# DefaultProject.net
KiCad netlist of a schematic drawn in Altium Designer
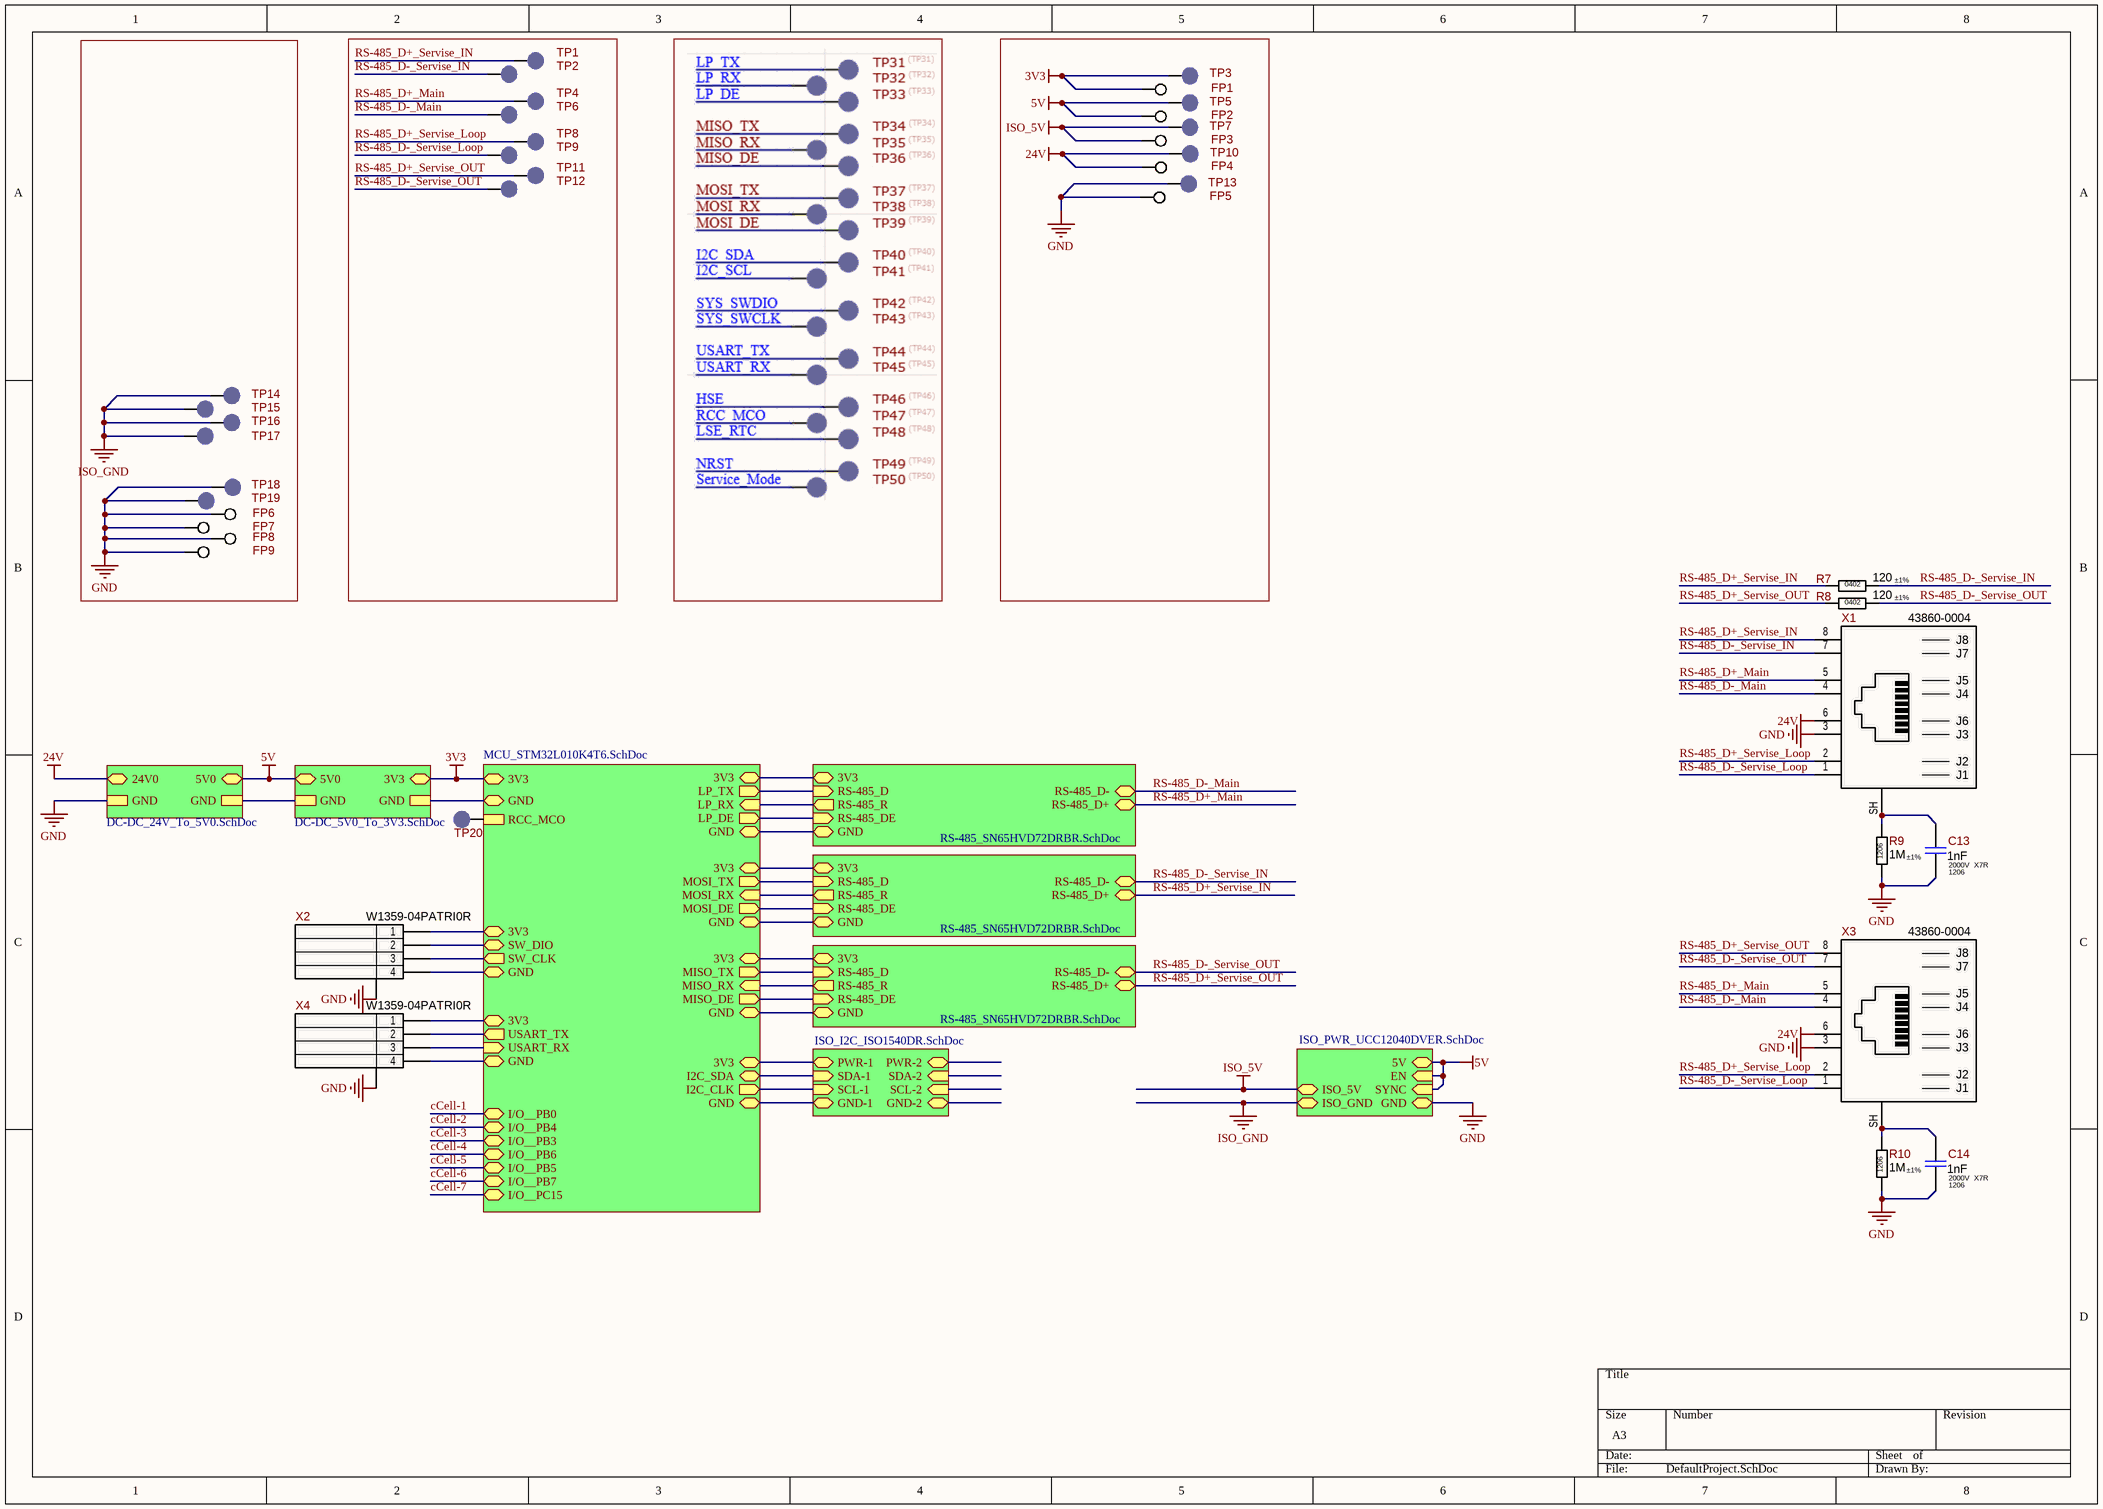
[diagram p0: DefaultProject.SchDoc]

(export (version "E")
  (design (tool "Eeschema 10.0.6"))
  (components
    (comp (ref "C13")
      (value "1nF")
      (footprint "CAP-1206(3216)X125T20")
      (description "1nF 2000V X7R ±10% 1206 Ceramic Capacitor RoHS")
      (fields
        (field (name "PACKAGE") "1206")
        (field (name "VOLTAGE") "2000V")
        (field (name "DIELECTRIC TYPE") "X7R")
        (field (name "PART NUMBER") "CC1206KKX7RDBB102")
        (field (name "MANUFACTURER") "Yageo")
      )
      (libsource (lib "EL.XXX.T01") (part "Capacitor-NonPolar"))
    )
    (comp (ref "C14")
      (value "1nF")
      (footprint "CAP-1206(3216)X125T20")
      (description "1nF 2000V X7R ±10% 1206 Ceramic Capacitor RoHS")
      (fields
        (field (name "PACKAGE") "1206")
        (field (name "VOLTAGE") "2000V")
        (field (name "DIELECTRIC TYPE") "X7R")
        (field (name "PART NUMBER") "CC1206KKX7RDBB102")
        (field (name "MANUFACTURER") "Yageo")
      )
      (libsource (lib "EL.XXX.T01") (part "Capacitor-NonPolar"))
    )
    (comp (ref "FP1")
      (value "PAD-1.1mm")
      (footprint "PAD-1.1mm")
      (description "1.1mm Pad for Plug-In or Receptacle")
      (fields (field (name "MANUFACTURER") "NONE"))
      (libsource (lib "EL.XXX.T01") (part "Pad"))
    )
    (comp (ref "FP2")
      (value "PAD-1.1mm")
      (footprint "PAD-1.1mm")
      (description "1.1mm Pad for Plug-In or Receptacle")
      (fields (field (name "MANUFACTURER") "NONE"))
      (libsource (lib "EL.XXX.T01") (part "Pad"))
    )
    (comp (ref "FP3")
      (value "PAD-1.1mm")
      (footprint "PAD-1.1mm")
      (description "1.1mm Pad for Plug-In or Receptacle")
      (fields (field (name "MANUFACTURER") "NONE"))
      (libsource (lib "EL.XXX.T01") (part "Pad"))
    )
    (comp (ref "FP4")
      (value "PAD-1.1mm")
      (footprint "PAD-1.1mm")
      (description "1.1mm Pad for Plug-In or Receptacle")
      (fields (field (name "MANUFACTURER") "NONE"))
      (libsource (lib "EL.XXX.T01") (part "Pad"))
    )
    (comp (ref "FP5")
      (value "PAD-1.1mm")
      (footprint "PAD-1.1mm")
      (description "1.1mm Pad for Plug-In or Receptacle")
      (fields (field (name "MANUFACTURER") "NONE"))
      (libsource (lib "EL.XXX.T01") (part "Pad"))
    )
    (comp (ref "FP6")
      (value "PAD-1.1mm")
      (footprint "PAD-1.1mm")
      (description "1.1mm Pad for Plug-In or Receptacle")
      (fields (field (name "MANUFACTURER") "NONE"))
      (libsource (lib "EL.XXX.T01") (part "Pad"))
    )
    (comp (ref "FP7")
      (value "PAD-1.1mm")
      (footprint "PAD-1.1mm")
      (description "1.1mm Pad for Plug-In or Receptacle")
      (fields (field (name "MANUFACTURER") "NONE"))
      (libsource (lib "EL.XXX.T01") (part "Pad"))
    )
    (comp (ref "FP8")
      (value "PAD-1.1mm")
      (footprint "PAD-1.1mm")
      (description "1.1mm Pad for Plug-In or Receptacle")
      (fields (field (name "MANUFACTURER") "NONE"))
      (libsource (lib "EL.XXX.T01") (part "Pad"))
    )
    (comp (ref "FP9")
      (value "PAD-1.1mm")
      (footprint "PAD-1.1mm")
      (description "1.1mm Pad for Plug-In or Receptacle")
      (fields (field (name "MANUFACTURER") "NONE"))
      (libsource (lib "EL.XXX.T01") (part "Pad"))
    )
    (comp (ref "R7")
      (value "120")
      (footprint "R_ANY_CHIP_0402_HI")
      (description "120 Ohms ±1% 1/16W 0402 Thick Film Resistor")
      (fields
        (field (name "TOLERANCE") "±1%")
        (field (name "PACKAGE") "0402")
        (field (name "PART NUMBER") "RC0402FR-07120RL")
        (field (name "MANUFACTURER") "Yageo")
      )
      (libsource (lib "EL.XXX.T01") (part "Resistor"))
    )
    (comp (ref "R8")
      (value "120")
      (footprint "R_ANY_CHIP_0402_HI")
      (description "120 Ohms ±1% 1/16W 0402 Thick Film Resistor")
      (fields
        (field (name "TOLERANCE") "±1%")
        (field (name "PACKAGE") "0402")
        (field (name "PART NUMBER") "RC0402FR-07120RL")
        (field (name "MANUFACTURER") "Yageo")
      )
      (libsource (lib "EL.XXX.T01") (part "Resistor"))
    )
    (comp (ref "R9")
      (value "1M")
      (footprint "CHV1206-Series")
      (description "1 MOhms ±1%, 1/4W 1206 Thick Film Resistor")
      (fields
        (field (name "TOLERANCE") "±1%")
        (field (name "PACKAGE") "1206")
        (field (name "PART NUMBER") "CHV1206-FX-1004ELF")
        (field (name "MANUFACTURER") "Bourns")
      )
      (libsource (lib "EL.XXX.T01") (part "Resistor"))
    )
    (comp (ref "R10")
      (value "1M")
      (footprint "CHV1206-Series")
      (description "1 MOhms ±1%, 1/4W 1206 Thick Film Resistor")
      (fields
        (field (name "TOLERANCE") "±1%")
        (field (name "PACKAGE") "1206")
        (field (name "PART NUMBER") "CHV1206-FX-1004ELF")
        (field (name "MANUFACTURER") "Bourns")
      )
      (libsource (lib "EL.XXX.T01") (part "Resistor"))
    )
    (comp (ref "TP1")
      (value "LED_LINK")
      (footprint "TP_SMD_2mm")
      (description "Test Point SMD Pad 1.0mm/1.5mm/2mm")
      (fields (field (name "PART NUMBER") "TP-PAD-SMD"))
      (libsource (lib "EL.XXX.T01") (part "Test-Point-SMD-1"))
    )
    (comp (ref "TP2")
      (value "LED_LINK")
      (footprint "TP_SMD_2mm")
      (description "Test Point SMD Pad 1.0mm/1.5mm/2mm")
      (fields (field (name "PART NUMBER") "TP-PAD-SMD"))
      (libsource (lib "EL.XXX.T01") (part "Test-Point-SMD-1"))
    )
    (comp (ref "TP3")
      (value "LED_LINK")
      (footprint "TP_SMD_2mm")
      (description "Test Point SMD Pad 1.0mm/1.5mm/2mm")
      (fields (field (name "PART NUMBER") "TP-PAD-SMD"))
      (libsource (lib "EL.XXX.T01") (part "Test-Point-SMD-1"))
    )
    (comp (ref "TP4")
      (value "LED_LINK")
      (footprint "TP_SMD_2mm")
      (description "Test Point SMD Pad 1.0mm/1.5mm/2mm")
      (fields (field (name "PART NUMBER") "TP-PAD-SMD"))
      (libsource (lib "EL.XXX.T01") (part "Test-Point-SMD-1"))
    )
    (comp (ref "TP5")
      (value "LED_LINK")
      (footprint "TP_SMD_2mm")
      (description "Test Point SMD Pad 1.0mm/1.5mm/2mm")
      (fields (field (name "PART NUMBER") "TP-PAD-SMD"))
      (libsource (lib "EL.XXX.T01") (part "Test-Point-SMD-1"))
    )
    (comp (ref "TP6")
      (value "LED_LINK")
      (footprint "TP_SMD_2mm")
      (description "Test Point SMD Pad 1.0mm/1.5mm/2mm")
      (fields (field (name "PART NUMBER") "TP-PAD-SMD"))
      (libsource (lib "EL.XXX.T01") (part "Test-Point-SMD-1"))
    )
    (comp (ref "TP7")
      (value "LED_LINK")
      (footprint "TP_SMD_2mm")
      (description "Test Point SMD Pad 1.0mm/1.5mm/2mm")
      (fields (field (name "PART NUMBER") "TP-PAD-SMD"))
      (libsource (lib "EL.XXX.T01") (part "Test-Point-SMD-1"))
    )
    (comp (ref "TP8")
      (value "LED_LINK")
      (footprint "TP_SMD_2mm")
      (description "Test Point SMD Pad 1.0mm/1.5mm/2mm")
      (fields (field (name "PART NUMBER") "TP-PAD-SMD"))
      (libsource (lib "EL.XXX.T01") (part "Test-Point-SMD-1"))
    )
    (comp (ref "TP9")
      (value "LED_LINK")
      (footprint "TP_SMD_2mm")
      (description "Test Point SMD Pad 1.0mm/1.5mm/2mm")
      (fields (field (name "PART NUMBER") "TP-PAD-SMD"))
      (libsource (lib "EL.XXX.T01") (part "Test-Point-SMD-1"))
    )
    (comp (ref "TP10")
      (value "LED_LINK")
      (footprint "TP_SMD_2mm")
      (description "Test Point SMD Pad 1.0mm/1.5mm/2mm")
      (fields (field (name "PART NUMBER") "TP-PAD-SMD"))
      (libsource (lib "EL.XXX.T01") (part "Test-Point-SMD-1"))
    )
    (comp (ref "TP11")
      (value "LED_LINK")
      (footprint "TP_SMD_2mm")
      (description "Test Point SMD Pad 1.0mm/1.5mm/2mm")
      (fields (field (name "PART NUMBER") "TP-PAD-SMD"))
      (libsource (lib "EL.XXX.T01") (part "Test-Point-SMD-1"))
    )
    (comp (ref "TP12")
      (value "LED_LINK")
      (footprint "TP_SMD_2mm")
      (description "Test Point SMD Pad 1.0mm/1.5mm/2mm")
      (fields (field (name "PART NUMBER") "TP-PAD-SMD"))
      (libsource (lib "EL.XXX.T01") (part "Test-Point-SMD-1"))
    )
    (comp (ref "TP13")
      (value "LED_LINK")
      (footprint "TP_SMD_2mm")
      (description "Test Point SMD Pad 1.0mm/1.5mm/2mm")
      (fields (field (name "PART NUMBER") "TP-PAD-SMD"))
      (libsource (lib "EL.XXX.T01") (part "Test-Point-SMD-1"))
    )
    (comp (ref "TP14")
      (value "LED_LINK")
      (footprint "TP_SMD_2mm")
      (description "Test Point SMD Pad 1.0mm/1.5mm/2mm")
      (fields (field (name "PART NUMBER") "TP-PAD-SMD"))
      (libsource (lib "EL.XXX.T01") (part "Test-Point-SMD-1"))
    )
    (comp (ref "TP15")
      (value "LED_LINK")
      (footprint "TP_SMD_2mm")
      (description "Test Point SMD Pad 1.0mm/1.5mm/2mm")
      (fields (field (name "PART NUMBER") "TP-PAD-SMD"))
      (libsource (lib "EL.XXX.T01") (part "Test-Point-SMD-1"))
    )
    (comp (ref "TP16")
      (value "LED_LINK")
      (footprint "TP_SMD_2mm")
      (description "Test Point SMD Pad 1.0mm/1.5mm/2mm")
      (fields (field (name "PART NUMBER") "TP-PAD-SMD"))
      (libsource (lib "EL.XXX.T01") (part "Test-Point-SMD-1"))
    )
    (comp (ref "TP17")
      (value "LED_LINK")
      (footprint "TP_SMD_2mm")
      (description "Test Point SMD Pad 1.0mm/1.5mm/2mm")
      (fields (field (name "PART NUMBER") "TP-PAD-SMD"))
      (libsource (lib "EL.XXX.T01") (part "Test-Point-SMD-1"))
    )
    (comp (ref "TP18")
      (value "LED_LINK")
      (footprint "TP_SMD_2mm")
      (description "Test Point SMD Pad 1.0mm/1.5mm/2mm")
      (fields (field (name "PART NUMBER") "TP-PAD-SMD"))
      (libsource (lib "EL.XXX.T01") (part "Test-Point-SMD-1"))
    )
    (comp (ref "TP19")
      (value "LED_LINK")
      (footprint "TP_SMD_2mm")
      (description "Test Point SMD Pad 1.0mm/1.5mm/2mm")
      (fields (field (name "PART NUMBER") "TP-PAD-SMD"))
      (libsource (lib "EL.XXX.T01") (part "Test-Point-SMD-1"))
    )
    (comp (ref "TP20")
      (value "LED_LINK")
      (footprint "TP_SMD_2mm")
      (description "Test Point SMD Pad 1.0mm/1.5mm/2mm")
      (fields (field (name "PART NUMBER") "TP-PAD-SMD"))
      (libsource (lib "EL.XXX.T01") (part "Test-Point-SMD-1"))
    )
    (comp (ref "X1")
      (value "43860-0004")
      (footprint "43860-0004")
      (description "RJ45 8P8C Shielded Cat 3 10 Base-T Connector")
      (fields (field (name "PART NUMBER") "43860-0004") (field (name "MANUFACTURER") "Molex"))
      (libsource (lib "EL.XXX.T01") (part "43860-0004"))
    )
    (comp (ref "X2")
      (value "W1359-04PATRI0R")
      (footprint "W1359-04PATXI0R_DBG")
      (description "1.25mm Wire-to-Board Header, Vertical, SMT, 4 pin")
      (fields
        (field (name "PART NUMBER") "W1359-04PATRI0R")
        (field (name "MANUFACTURER") "Hsuan Mao Technology")
      )
      (libsource (lib "EL.XXX.T01") (part "General-4-Pin-MP"))
    )
    (comp (ref "X3")
      (value "43860-0004")
      (footprint "43860-0004")
      (description "RJ45 8P8C Shielded Cat 3 10 Base-T Connector")
      (fields (field (name "PART NUMBER") "43860-0004") (field (name "MANUFACTURER") "Molex"))
      (libsource (lib "EL.XXX.T01") (part "43860-0004"))
    )
    (comp (ref "X4")
      (value "W1359-04PATRI0R")
      (footprint "W1359-04PATXI0R_DBG")
      (description "1.25mm Wire-to-Board Header, Vertical, SMT, 4 pin")
      (fields
        (field (name "PART NUMBER") "W1359-04PATRI0R")
        (field (name "MANUFACTURER") "Hsuan Mao Technology")
      )
      (libsource (lib "EL.XXX.T01") (part "General-4-Pin-MP"))
    )
  )
  (nets
    (net (code "3") (name "/3V3_2") (class "Default")
      (node (ref "X2") (pin "1") (pinfunction "1_1") (pintype "passive"))
    )
    (net (code "5") (name "/3V3_4") (class "Default")
      (node (ref "X4") (pin "1") (pinfunction "1_1") (pintype "passive"))
    )
    (net (code "12") (name "/GND_1") (class "Default")
      (node (ref "X4") (pin "4") (pinfunction "4_4") (pintype "passive"))
    )
    (net (code "18") (name "/GND_7") (class "Default")
      (node (ref "X2") (pin "4") (pinfunction "4_4") (pintype "passive"))
    )
    (net (code "34") (name "/RCC_MCO") (class "Default") (node (ref "TP20") (pin "1") (pintype "passive")))
    (net (code "36") (name "/RS-485_D+_Main") (class "Default")
      (node (ref "TP4") (pin "1") (pintype "passive"))
      (node (ref "X1") (pin "5") (pinfunction "CT_5") (pintype "passive"))
      (node (ref "X3") (pin "5") (pinfunction "CT_5") (pintype "passive"))
    )
    (net (code "37") (name "/RS-485_D+_Servise_IN") (class "Default")
      (node (ref "R7") (pin "1") (pintype "passive"))
      (node (ref "TP1") (pin "1") (pintype "passive"))
      (node (ref "X1") (pin "8") (pinfunction "TD2+_8") (pintype "passive"))
    )
    (net (code "38") (name "/RS-485_D+_Servise_Loop") (class "Default")
      (node (ref "TP8") (pin "1") (pintype "passive"))
      (node (ref "X1") (pin "2") (pinfunction "TD4+_2") (pintype "passive"))
      (node (ref "X3") (pin "2") (pinfunction "TD4+_2") (pintype "passive"))
    )
    (net (code "39") (name "/RS-485_D+_Servise_OUT") (class "Default")
      (node (ref "R8") (pin "1") (pintype "passive"))
      (node (ref "TP11") (pin "1") (pintype "passive"))
      (node (ref "X3") (pin "8") (pinfunction "TD2+_8") (pintype "passive"))
    )
    (net (code "40") (name "/RS-485_D-_Main") (class "Default")
      (node (ref "TP6") (pin "1") (pintype "passive"))
      (node (ref "X1") (pin "4") (pinfunction "TD3+_4") (pintype "passive"))
      (node (ref "X3") (pin "4") (pinfunction "TD3+_4") (pintype "passive"))
    )
    (net (code "41") (name "/RS-485_D-_Servise_IN") (class "Default")
      (node (ref "R7") (pin "2") (pintype "passive"))
      (node (ref "TP2") (pin "1") (pintype "passive"))
      (node (ref "X1") (pin "7") (pinfunction "TD2-_7") (pintype "passive"))
    )
    (net (code "42") (name "/RS-485_D-_Servise_Loop") (class "Default")
      (node (ref "TP9") (pin "1") (pintype "passive"))
      (node (ref "X1") (pin "1") (pinfunction "TD4-_1") (pintype "passive"))
      (node (ref "X3") (pin "1") (pinfunction "TD4-_1") (pintype "passive"))
    )
    (net (code "43") (name "/RS-485_D-_Servise_OUT") (class "Default")
      (node (ref "R8") (pin "2") (pintype "passive"))
      (node (ref "TP12") (pin "1") (pintype "passive"))
      (node (ref "X3") (pin "7") (pinfunction "TD2-_7") (pintype "passive"))
    )
    (net (code "54") (name "/SW_CLK") (class "Default")
      (node (ref "X2") (pin "3") (pinfunction "3_3") (pintype "passive"))
    )
    (net (code "55") (name "/SW_DIO") (class "Default")
      (node (ref "X2") (pin "2") (pinfunction "2_2") (pintype "passive"))
    )
    (net (code "56") (name "/USART_RX") (class "Default")
      (node (ref "X4") (pin "3") (pinfunction "3_3") (pintype "passive"))
    )
    (net (code "57") (name "/USART_TX") (class "Default")
      (node (ref "X4") (pin "2") (pinfunction "2_2") (pintype "passive"))
    )
    (net (code "65") (name "3V3") (class "Default")
      (node (ref "FP1") (pin "1") (pintype "passive"))
      (node (ref "TP3") (pin "1") (pintype "passive"))
    )
    (net (code "66") (name "5V") (class "Default")
      (node (ref "FP2") (pin "1") (pintype "passive"))
      (node (ref "TP5") (pin "1") (pintype "passive"))
    )
    (net (code "67") (name "24V") (class "Default")
      (node (ref "FP4") (pin "1") (pintype "passive"))
      (node (ref "TP10") (pin "1") (pintype "passive"))
      (node (ref "X1") (pin "6") (pinfunction "CT_6") (pintype "passive"))
      (node (ref "X3") (pin "6") (pinfunction "CT_6") (pintype "passive"))
    )
    (net (code "68") (name "GND") (class "Default")
      (node (ref "C13") (pin "2") (pinfunction "2_2") (pintype "passive"))
      (node (ref "C14") (pin "2") (pinfunction "2_2") (pintype "passive"))
      (node (ref "FP5") (pin "1") (pintype "passive"))
      (node (ref "FP6") (pin "1") (pintype "passive"))
      (node (ref "FP7") (pin "1") (pintype "passive"))
      (node (ref "FP8") (pin "1") (pintype "passive"))
      (node (ref "FP9") (pin "1") (pintype "passive"))
      (node (ref "R10") (pin "2") (pintype "passive"))
      (node (ref "R9") (pin "2") (pintype "passive"))
      (node (ref "TP13") (pin "1") (pintype "passive"))
      (node (ref "TP18") (pin "1") (pintype "passive"))
      (node (ref "TP19") (pin "1") (pintype "passive"))
      (node (ref "X1") (pin "3") (pinfunction "TD3-_3") (pintype "passive"))
      (node (ref "X2") (pin "MP") (pinfunction "MountPad_MP") (pintype "passive"))
      (node (ref "X3") (pin "3") (pinfunction "TD3-_3") (pintype "passive"))
      (node (ref "X4") (pin "MP") (pinfunction "MountPad_MP") (pintype "passive"))
    )
    (net (code "69") (name "ISO_5V") (class "Default")
      (node (ref "FP3") (pin "1") (pintype "passive"))
      (node (ref "TP7") (pin "1") (pintype "passive"))
    )
    (net (code "70") (name "ISO_GND") (class "Default")
      (node (ref "TP14") (pin "1") (pintype "passive"))
      (node (ref "TP15") (pin "1") (pintype "passive"))
      (node (ref "TP16") (pin "1") (pintype "passive"))
      (node (ref "TP17") (pin "1") (pintype "passive"))
    )
    (net (code "71") (name "Net-(X1-Shield)") (class "Default")
      (node (ref "C13") (pin "1") (pinfunction "1_1") (pintype "passive"))
      (node (ref "R9") (pin "1") (pintype "passive"))
      (node (ref "X1") (pin "SH") (pinfunction "Shield_SH") (pintype "passive"))
    )
    (net (code "72") (name "Net-(X3-Shield)") (class "Default")
      (node (ref "C14") (pin "1") (pinfunction "1_1") (pintype "passive"))
      (node (ref "R10") (pin "1") (pintype "passive"))
      (node (ref "X3") (pin "SH") (pinfunction "Shield_SH") (pintype "passive"))
    )
  )
)
